# Level_Translators.net
KiCad netlist of a schematic drawn in Altium Designer
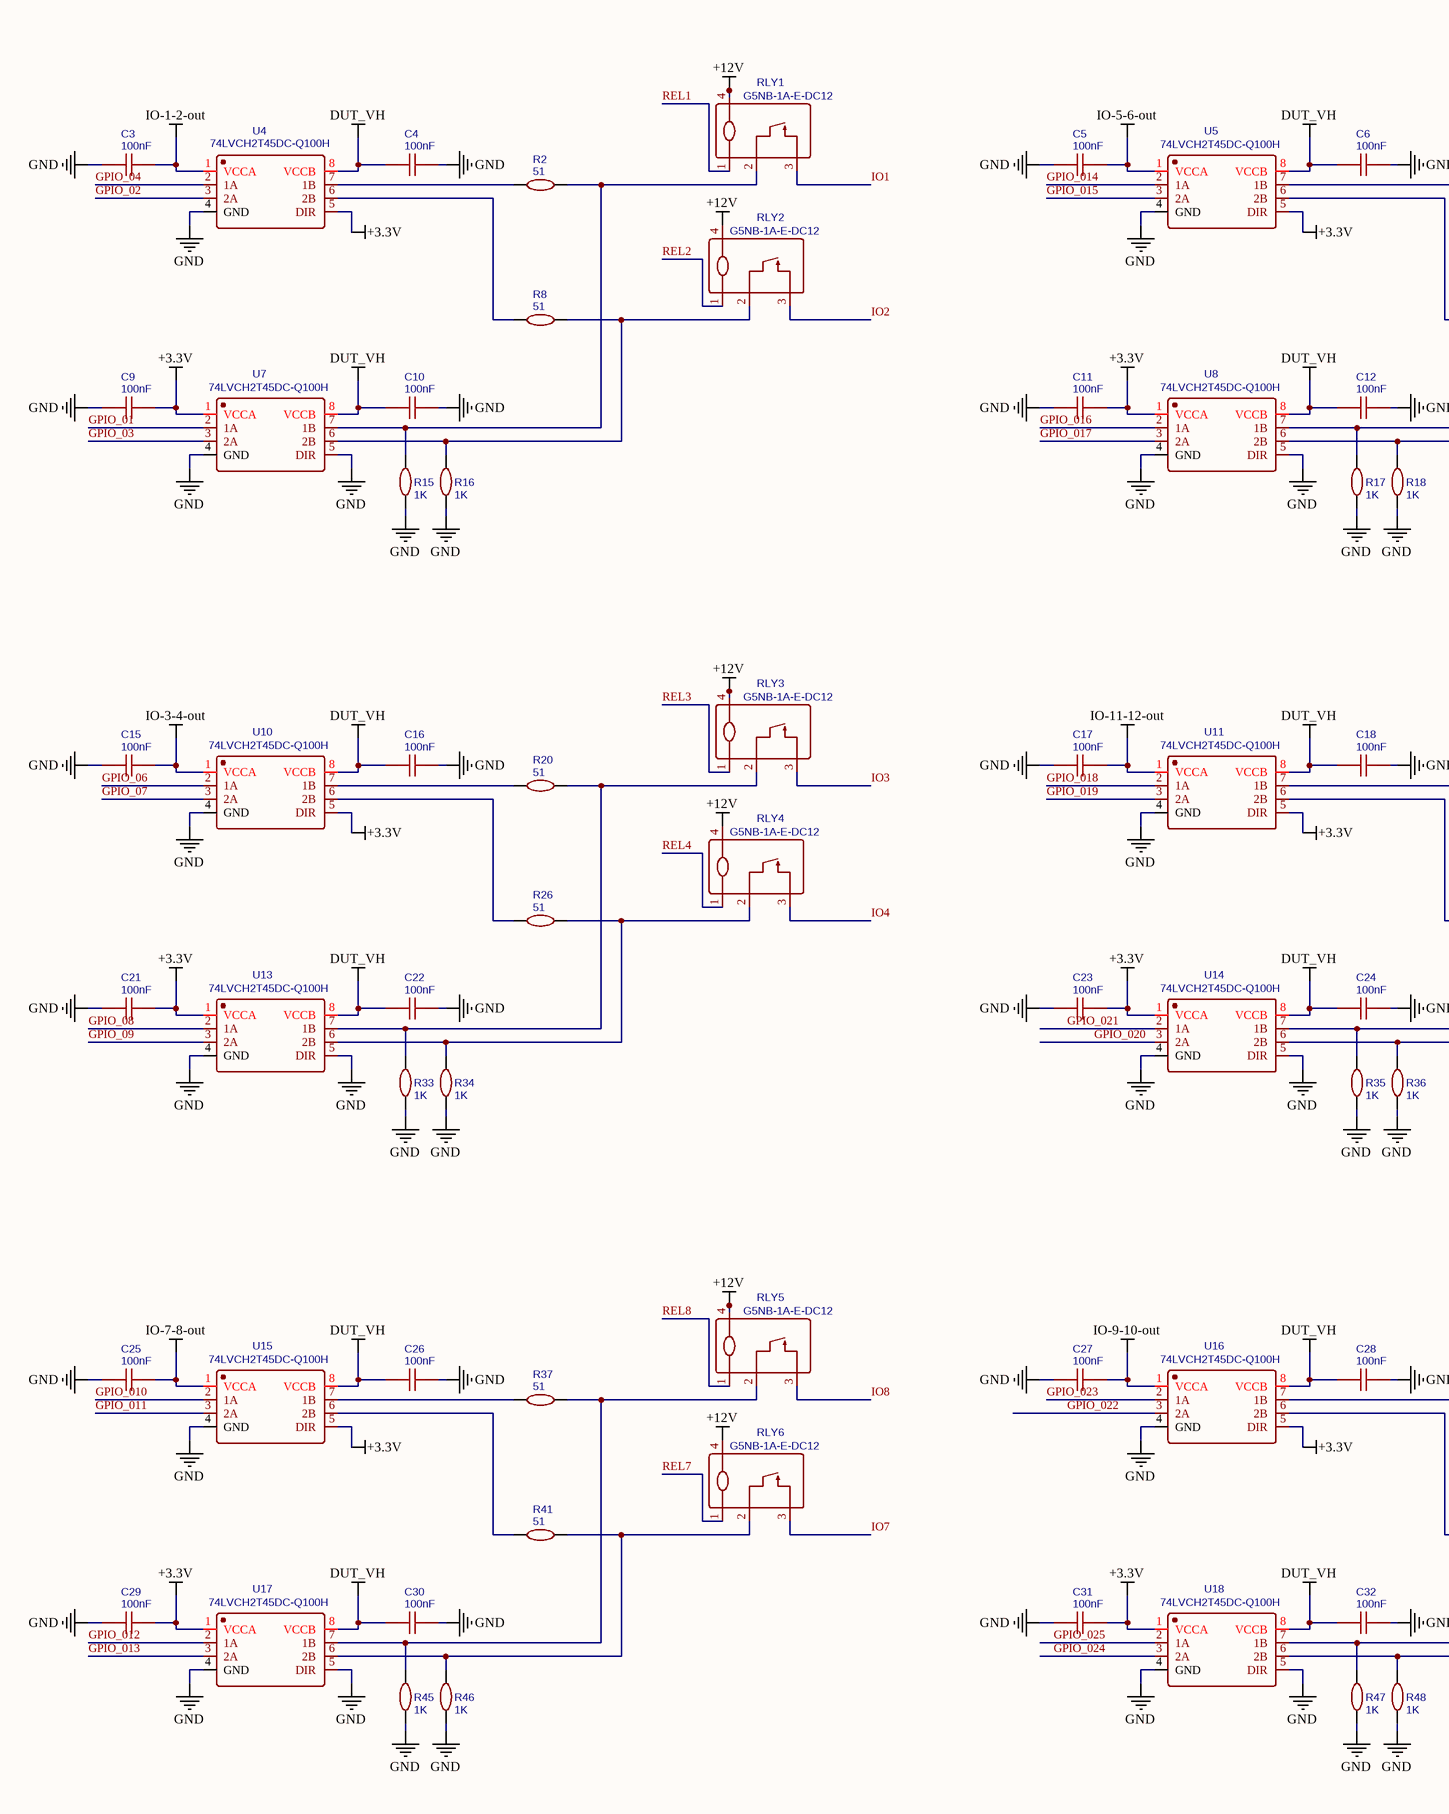
[diagram p0: Level Translators.SchDoc, left]
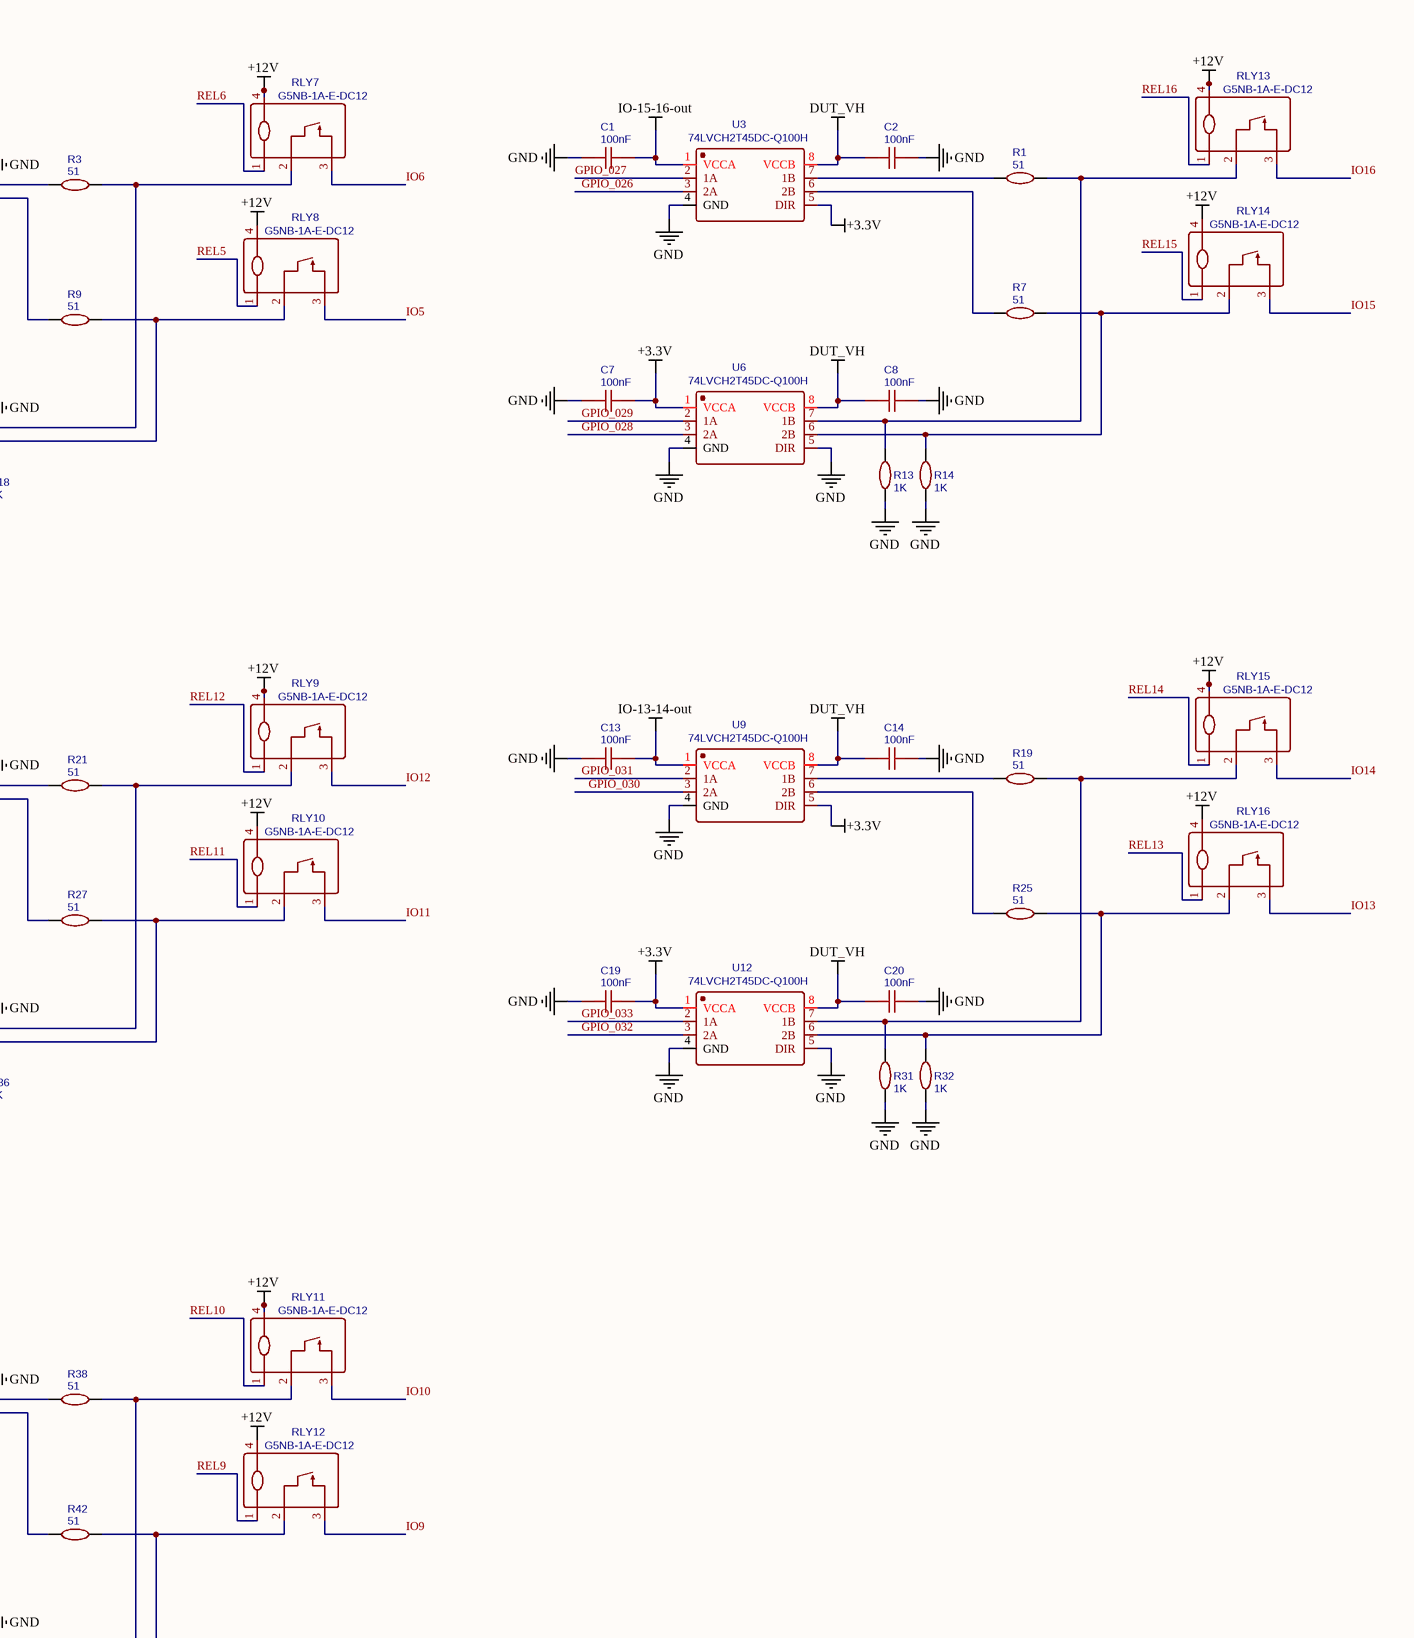
[diagram p1: Level Translators.SchDoc, right]

(export (version "E")
  (design (tool "Eeschema 10.0.6"))
  (components
    (comp (ref "C1")
      (value "100nF")
      (footprint "C0603")
      (fields
        (field (name "MANUFACTURER") "YAGEO")
        (field (name "MANUFACTURE PART NUMBER") "CC0603KRX7R9BB104")
      )
      (libsource (lib "FPGA Interface Board") (part "100nF"))
    )
    (comp (ref "C2")
      (value "100nF")
      (footprint "C0603")
      (fields
        (field (name "MANUFACTURER") "YAGEO")
        (field (name "MANUFACTURE PART NUMBER") "CC0603KRX7R9BB104")
      )
      (libsource (lib "FPGA Interface Board") (part "100nF"))
    )
    (comp (ref "C3")
      (value "100nF")
      (footprint "C0603")
      (fields
        (field (name "MANUFACTURER") "YAGEO")
        (field (name "MANUFACTURE PART NUMBER") "CC0603KRX7R9BB104")
      )
      (libsource (lib "FPGA Interface Board") (part "100nF"))
    )
    (comp (ref "C4")
      (value "100nF")
      (footprint "C0603")
      (fields
        (field (name "MANUFACTURER") "YAGEO")
        (field (name "MANUFACTURE PART NUMBER") "CC0603KRX7R9BB104")
      )
      (libsource (lib "FPGA Interface Board") (part "100nF"))
    )
    (comp (ref "C5")
      (value "100nF")
      (footprint "C0603")
      (fields
        (field (name "MANUFACTURER") "YAGEO")
        (field (name "MANUFACTURE PART NUMBER") "CC0603KRX7R9BB104")
      )
      (libsource (lib "FPGA Interface Board") (part "100nF"))
    )
    (comp (ref "C6")
      (value "100nF")
      (footprint "C0603")
      (fields
        (field (name "MANUFACTURER") "YAGEO")
        (field (name "MANUFACTURE PART NUMBER") "CC0603KRX7R9BB104")
      )
      (libsource (lib "FPGA Interface Board") (part "100nF"))
    )
    (comp (ref "C7")
      (value "100nF")
      (footprint "C0603")
      (fields
        (field (name "MANUFACTURER") "YAGEO")
        (field (name "MANUFACTURE PART NUMBER") "CC0603KRX7R9BB104")
      )
      (libsource (lib "FPGA Interface Board") (part "100nF"))
    )
    (comp (ref "C8")
      (value "100nF")
      (footprint "C0603")
      (fields
        (field (name "MANUFACTURER") "YAGEO")
        (field (name "MANUFACTURE PART NUMBER") "CC0603KRX7R9BB104")
      )
      (libsource (lib "FPGA Interface Board") (part "100nF"))
    )
    (comp (ref "C9")
      (value "100nF")
      (footprint "C0603")
      (fields
        (field (name "MANUFACTURER") "YAGEO")
        (field (name "MANUFACTURE PART NUMBER") "CC0603KRX7R9BB104")
      )
      (libsource (lib "FPGA Interface Board") (part "100nF"))
    )
    (comp (ref "C10")
      (value "100nF")
      (footprint "C0603")
      (fields
        (field (name "MANUFACTURER") "YAGEO")
        (field (name "MANUFACTURE PART NUMBER") "CC0603KRX7R9BB104")
      )
      (libsource (lib "FPGA Interface Board") (part "100nF"))
    )
    (comp (ref "C11")
      (value "100nF")
      (footprint "C0603")
      (fields
        (field (name "MANUFACTURER") "YAGEO")
        (field (name "MANUFACTURE PART NUMBER") "CC0603KRX7R9BB104")
      )
      (libsource (lib "FPGA Interface Board") (part "100nF"))
    )
    (comp (ref "C12")
      (value "100nF")
      (footprint "C0603")
      (fields
        (field (name "MANUFACTURER") "YAGEO")
        (field (name "MANUFACTURE PART NUMBER") "CC0603KRX7R9BB104")
      )
      (libsource (lib "FPGA Interface Board") (part "100nF"))
    )
    (comp (ref "C13")
      (value "100nF")
      (footprint "C0603")
      (fields
        (field (name "MANUFACTURER") "YAGEO")
        (field (name "MANUFACTURE PART NUMBER") "CC0603KRX7R9BB104")
      )
      (libsource (lib "FPGA Interface Board") (part "100nF"))
    )
    (comp (ref "C14")
      (value "100nF")
      (footprint "C0603")
      (fields
        (field (name "MANUFACTURER") "YAGEO")
        (field (name "MANUFACTURE PART NUMBER") "CC0603KRX7R9BB104")
      )
      (libsource (lib "FPGA Interface Board") (part "100nF"))
    )
    (comp (ref "C15")
      (value "100nF")
      (footprint "C0603")
      (fields
        (field (name "MANUFACTURER") "YAGEO")
        (field (name "MANUFACTURE PART NUMBER") "CC0603KRX7R9BB104")
      )
      (libsource (lib "FPGA Interface Board") (part "100nF"))
    )
    (comp (ref "C16")
      (value "100nF")
      (footprint "C0603")
      (fields
        (field (name "MANUFACTURER") "YAGEO")
        (field (name "MANUFACTURE PART NUMBER") "CC0603KRX7R9BB104")
      )
      (libsource (lib "FPGA Interface Board") (part "100nF"))
    )
    (comp (ref "C17")
      (value "100nF")
      (footprint "C0603")
      (fields
        (field (name "MANUFACTURER") "YAGEO")
        (field (name "MANUFACTURE PART NUMBER") "CC0603KRX7R9BB104")
      )
      (libsource (lib "FPGA Interface Board") (part "100nF"))
    )
    (comp (ref "C18")
      (value "100nF")
      (footprint "C0603")
      (fields
        (field (name "MANUFACTURER") "YAGEO")
        (field (name "MANUFACTURE PART NUMBER") "CC0603KRX7R9BB104")
      )
      (libsource (lib "FPGA Interface Board") (part "100nF"))
    )
    (comp (ref "C19")
      (value "100nF")
      (footprint "C0603")
      (fields
        (field (name "MANUFACTURER") "YAGEO")
        (field (name "MANUFACTURE PART NUMBER") "CC0603KRX7R9BB104")
      )
      (libsource (lib "FPGA Interface Board") (part "100nF"))
    )
    (comp (ref "C20")
      (value "100nF")
      (footprint "C0603")
      (fields
        (field (name "MANUFACTURER") "YAGEO")
        (field (name "MANUFACTURE PART NUMBER") "CC0603KRX7R9BB104")
      )
      (libsource (lib "FPGA Interface Board") (part "100nF"))
    )
    (comp (ref "C21")
      (value "100nF")
      (footprint "C0603")
      (fields
        (field (name "MANUFACTURER") "YAGEO")
        (field (name "MANUFACTURE PART NUMBER") "CC0603KRX7R9BB104")
      )
      (libsource (lib "FPGA Interface Board") (part "100nF"))
    )
    (comp (ref "C22")
      (value "100nF")
      (footprint "C0603")
      (fields
        (field (name "MANUFACTURER") "YAGEO")
        (field (name "MANUFACTURE PART NUMBER") "CC0603KRX7R9BB104")
      )
      (libsource (lib "FPGA Interface Board") (part "100nF"))
    )
    (comp (ref "C23")
      (value "100nF")
      (footprint "C0603")
      (fields
        (field (name "MANUFACTURER") "YAGEO")
        (field (name "MANUFACTURE PART NUMBER") "CC0603KRX7R9BB104")
      )
      (libsource (lib "FPGA Interface Board") (part "100nF"))
    )
    (comp (ref "C24")
      (value "100nF")
      (footprint "C0603")
      (fields
        (field (name "MANUFACTURER") "YAGEO")
        (field (name "MANUFACTURE PART NUMBER") "CC0603KRX7R9BB104")
      )
      (libsource (lib "FPGA Interface Board") (part "100nF"))
    )
    (comp (ref "C25")
      (value "100nF")
      (footprint "C0603")
      (fields
        (field (name "MANUFACTURER") "YAGEO")
        (field (name "MANUFACTURE PART NUMBER") "CC0603KRX7R9BB104")
      )
      (libsource (lib "FPGA Interface Board") (part "100nF"))
    )
    (comp (ref "C26")
      (value "100nF")
      (footprint "C0603")
      (fields
        (field (name "MANUFACTURER") "YAGEO")
        (field (name "MANUFACTURE PART NUMBER") "CC0603KRX7R9BB104")
      )
      (libsource (lib "FPGA Interface Board") (part "100nF"))
    )
    (comp (ref "C27")
      (value "100nF")
      (footprint "C0603")
      (fields
        (field (name "MANUFACTURER") "YAGEO")
        (field (name "MANUFACTURE PART NUMBER") "CC0603KRX7R9BB104")
      )
      (libsource (lib "FPGA Interface Board") (part "100nF"))
    )
    (comp (ref "C28")
      (value "100nF")
      (footprint "C0603")
      (fields
        (field (name "MANUFACTURER") "YAGEO")
        (field (name "MANUFACTURE PART NUMBER") "CC0603KRX7R9BB104")
      )
      (libsource (lib "FPGA Interface Board") (part "100nF"))
    )
    (comp (ref "C29")
      (value "100nF")
      (footprint "C0603")
      (fields
        (field (name "MANUFACTURER") "YAGEO")
        (field (name "MANUFACTURE PART NUMBER") "CC0603KRX7R9BB104")
      )
      (libsource (lib "FPGA Interface Board") (part "100nF"))
    )
    (comp (ref "C30")
      (value "100nF")
      (footprint "C0603")
      (fields
        (field (name "MANUFACTURER") "YAGEO")
        (field (name "MANUFACTURE PART NUMBER") "CC0603KRX7R9BB104")
      )
      (libsource (lib "FPGA Interface Board") (part "100nF"))
    )
    (comp (ref "C31")
      (value "100nF")
      (footprint "C0603")
      (fields
        (field (name "MANUFACTURER") "YAGEO")
        (field (name "MANUFACTURE PART NUMBER") "CC0603KRX7R9BB104")
      )
      (libsource (lib "FPGA Interface Board") (part "100nF"))
    )
    (comp (ref "C32")
      (value "100nF")
      (footprint "C0603")
      (fields
        (field (name "MANUFACTURER") "YAGEO")
        (field (name "MANUFACTURE PART NUMBER") "CC0603KRX7R9BB104")
      )
      (libsource (lib "FPGA Interface Board") (part "100nF"))
    )
    (comp (ref "R1")
      (value "51")
      (footprint "R0603")
      (fields
        (field (name "MANUFACTURER") "UniOhm")
        (field (name "MANUFACTURE PART NUMBER") "0603WAF510JT5E")
      )
      (libsource (lib "FPGA Interface Board") (part "51"))
    )
    (comp (ref "R2")
      (value "51")
      (footprint "R0603")
      (fields
        (field (name "MANUFACTURER") "UniOhm")
        (field (name "MANUFACTURE PART NUMBER") "0603WAF510JT5E")
      )
      (libsource (lib "FPGA Interface Board") (part "51"))
    )
    (comp (ref "R3")
      (value "51")
      (footprint "R0603")
      (fields
        (field (name "MANUFACTURER") "UniOhm")
        (field (name "MANUFACTURE PART NUMBER") "0603WAF510JT5E")
      )
      (libsource (lib "FPGA Interface Board") (part "51"))
    )
    (comp (ref "R7")
      (value "51")
      (footprint "R0603")
      (fields
        (field (name "MANUFACTURER") "UniOhm")
        (field (name "MANUFACTURE PART NUMBER") "0603WAF510JT5E")
      )
      (libsource (lib "FPGA Interface Board") (part "51"))
    )
    (comp (ref "R8")
      (value "51")
      (footprint "R0603")
      (fields
        (field (name "MANUFACTURER") "UniOhm")
        (field (name "MANUFACTURE PART NUMBER") "0603WAF510JT5E")
      )
      (libsource (lib "FPGA Interface Board") (part "51"))
    )
    (comp (ref "R9")
      (value "51")
      (footprint "R0603")
      (fields
        (field (name "MANUFACTURER") "UniOhm")
        (field (name "MANUFACTURE PART NUMBER") "0603WAF510JT5E")
      )
      (libsource (lib "FPGA Interface Board") (part "51"))
    )
    (comp (ref "R13")
      (value "1K")
      (footprint "R0603")
      (fields (field (name "MANUFACTURE PART NUMBER") "RC0603FR-071KL") (field (name "MANUFACTURER") "YAGEO"))
      (libsource (lib "FPGA Interface Board") (part "1K"))
    )
    (comp (ref "R14")
      (value "1K")
      (footprint "R0603")
      (fields (field (name "MANUFACTURE PART NUMBER") "RC0603FR-071KL") (field (name "MANUFACTURER") "YAGEO"))
      (libsource (lib "FPGA Interface Board") (part "1K"))
    )
    (comp (ref "R15")
      (value "1K")
      (footprint "R0603")
      (fields (field (name "MANUFACTURE PART NUMBER") "RC0603FR-071KL") (field (name "MANUFACTURER") "YAGEO"))
      (libsource (lib "FPGA Interface Board") (part "1K"))
    )
    (comp (ref "R16")
      (value "1K")
      (footprint "R0603")
      (fields (field (name "MANUFACTURE PART NUMBER") "RC0603FR-071KL") (field (name "MANUFACTURER") "YAGEO"))
      (libsource (lib "FPGA Interface Board") (part "1K"))
    )
    (comp (ref "R17")
      (value "1K")
      (footprint "R0603")
      (fields (field (name "MANUFACTURE PART NUMBER") "RC0603FR-071KL") (field (name "MANUFACTURER") "YAGEO"))
      (libsource (lib "FPGA Interface Board") (part "1K"))
    )
    (comp (ref "R18")
      (value "1K")
      (footprint "R0603")
      (fields (field (name "MANUFACTURE PART NUMBER") "RC0603FR-071KL") (field (name "MANUFACTURER") "YAGEO"))
      (libsource (lib "FPGA Interface Board") (part "1K"))
    )
    (comp (ref "R19")
      (value "51")
      (footprint "R0603")
      (fields
        (field (name "MANUFACTURER") "UniOhm")
        (field (name "MANUFACTURE PART NUMBER") "0603WAF510JT5E")
      )
      (libsource (lib "FPGA Interface Board") (part "51"))
    )
    (comp (ref "R20")
      (value "51")
      (footprint "R0603")
      (fields
        (field (name "MANUFACTURER") "UniOhm")
        (field (name "MANUFACTURE PART NUMBER") "0603WAF510JT5E")
      )
      (libsource (lib "FPGA Interface Board") (part "51"))
    )
    (comp (ref "R21")
      (value "51")
      (footprint "R0603")
      (fields
        (field (name "MANUFACTURER") "UniOhm")
        (field (name "MANUFACTURE PART NUMBER") "0603WAF510JT5E")
      )
      (libsource (lib "FPGA Interface Board") (part "51"))
    )
    (comp (ref "R25")
      (value "51")
      (footprint "R0603")
      (fields
        (field (name "MANUFACTURER") "UniOhm")
        (field (name "MANUFACTURE PART NUMBER") "0603WAF510JT5E")
      )
      (libsource (lib "FPGA Interface Board") (part "51"))
    )
    (comp (ref "R26")
      (value "51")
      (footprint "R0603")
      (fields
        (field (name "MANUFACTURER") "UniOhm")
        (field (name "MANUFACTURE PART NUMBER") "0603WAF510JT5E")
      )
      (libsource (lib "FPGA Interface Board") (part "51"))
    )
    (comp (ref "R27")
      (value "51")
      (footprint "R0603")
      (fields
        (field (name "MANUFACTURER") "UniOhm")
        (field (name "MANUFACTURE PART NUMBER") "0603WAF510JT5E")
      )
      (libsource (lib "FPGA Interface Board") (part "51"))
    )
    (comp (ref "R31")
      (value "1K")
      (footprint "R0603")
      (fields (field (name "MANUFACTURE PART NUMBER") "RC0603FR-071KL") (field (name "MANUFACTURER") "YAGEO"))
      (libsource (lib "FPGA Interface Board") (part "1K"))
    )
    (comp (ref "R32")
      (value "1K")
      (footprint "R0603")
      (fields (field (name "MANUFACTURE PART NUMBER") "RC0603FR-071KL") (field (name "MANUFACTURER") "YAGEO"))
      (libsource (lib "FPGA Interface Board") (part "1K"))
    )
    (comp (ref "R33")
      (value "1K")
      (footprint "R0603")
      (fields (field (name "MANUFACTURE PART NUMBER") "RC0603FR-071KL") (field (name "MANUFACTURER") "YAGEO"))
      (libsource (lib "FPGA Interface Board") (part "1K"))
    )
    (comp (ref "R34")
      (value "1K")
      (footprint "R0603")
      (fields (field (name "MANUFACTURE PART NUMBER") "RC0603FR-071KL") (field (name "MANUFACTURER") "YAGEO"))
      (libsource (lib "FPGA Interface Board") (part "1K"))
    )
    (comp (ref "R35")
      (value "1K")
      (footprint "R0603")
      (fields (field (name "MANUFACTURE PART NUMBER") "RC0603FR-071KL") (field (name "MANUFACTURER") "YAGEO"))
      (libsource (lib "FPGA Interface Board") (part "1K"))
    )
    (comp (ref "R36")
      (value "1K")
      (footprint "R0603")
      (fields (field (name "MANUFACTURE PART NUMBER") "RC0603FR-071KL") (field (name "MANUFACTURER") "YAGEO"))
      (libsource (lib "FPGA Interface Board") (part "1K"))
    )
    (comp (ref "R37")
      (value "51")
      (footprint "R0603")
      (fields
        (field (name "MANUFACTURER") "UniOhm")
        (field (name "MANUFACTURE PART NUMBER") "0603WAF510JT5E")
      )
      (libsource (lib "FPGA Interface Board") (part "51"))
    )
    (comp (ref "R38")
      (value "51")
      (footprint "R0603")
      (fields
        (field (name "MANUFACTURER") "UniOhm")
        (field (name "MANUFACTURE PART NUMBER") "0603WAF510JT5E")
      )
      (libsource (lib "FPGA Interface Board") (part "51"))
    )
    (comp (ref "R41")
      (value "51")
      (footprint "R0603")
      (fields
        (field (name "MANUFACTURER") "UniOhm")
        (field (name "MANUFACTURE PART NUMBER") "0603WAF510JT5E")
      )
      (libsource (lib "FPGA Interface Board") (part "51"))
    )
    (comp (ref "R42")
      (value "51")
      (footprint "R0603")
      (fields
        (field (name "MANUFACTURER") "UniOhm")
        (field (name "MANUFACTURE PART NUMBER") "0603WAF510JT5E")
      )
      (libsource (lib "FPGA Interface Board") (part "51"))
    )
    (comp (ref "R45")
      (value "1K")
      (footprint "R0603")
      (fields (field (name "MANUFACTURE PART NUMBER") "RC0603FR-071KL") (field (name "MANUFACTURER") "YAGEO"))
      (libsource (lib "FPGA Interface Board") (part "1K"))
    )
    (comp (ref "R46")
      (value "1K")
      (footprint "R0603")
      (fields (field (name "MANUFACTURE PART NUMBER") "RC0603FR-071KL") (field (name "MANUFACTURER") "YAGEO"))
      (libsource (lib "FPGA Interface Board") (part "1K"))
    )
    (comp (ref "R47")
      (value "1K")
      (footprint "R0603")
      (fields (field (name "MANUFACTURE PART NUMBER") "RC0603FR-071KL") (field (name "MANUFACTURER") "YAGEO"))
      (libsource (lib "FPGA Interface Board") (part "1K"))
    )
    (comp (ref "R48")
      (value "1K")
      (footprint "R0603")
      (fields (field (name "MANUFACTURE PART NUMBER") "RC0603FR-071KL") (field (name "MANUFACTURER") "YAGEO"))
      (libsource (lib "FPGA Interface Board") (part "1K"))
    )
    (comp (ref "RLY1")
      (value "G5NB-1A-E-DC12")
      (footprint "RELAY-TH_G5NB-1A-E-DCXX")
      (fields (field (name "MANUFACTURER") "Omron Electronics") (field (name "CONTRIBUTOR") "LCSC"))
      (libsource (lib "FPGA Interface Board") (part "G5NB-1A-E-DC12"))
    )
    (comp (ref "RLY2")
      (value "G5NB-1A-E-DC12")
      (footprint "RELAY-TH_G5NB-1A-E-DCXX")
      (fields (field (name "MANUFACTURER") "Omron Electronics") (field (name "CONTRIBUTOR") "LCSC"))
      (libsource (lib "FPGA Interface Board") (part "G5NB-1A-E-DC12"))
    )
    (comp (ref "RLY3")
      (value "G5NB-1A-E-DC12")
      (footprint "RELAY-TH_G5NB-1A-E-DCXX")
      (fields (field (name "MANUFACTURER") "Omron Electronics") (field (name "CONTRIBUTOR") "LCSC"))
      (libsource (lib "FPGA Interface Board") (part "G5NB-1A-E-DC12"))
    )
    (comp (ref "RLY4")
      (value "G5NB-1A-E-DC12")
      (footprint "RELAY-TH_G5NB-1A-E-DCXX")
      (fields (field (name "MANUFACTURER") "Omron Electronics") (field (name "CONTRIBUTOR") "LCSC"))
      (libsource (lib "FPGA Interface Board") (part "G5NB-1A-E-DC12"))
    )
    (comp (ref "RLY5")
      (value "G5NB-1A-E-DC12")
      (footprint "RELAY-TH_G5NB-1A-E-DCXX")
      (fields (field (name "MANUFACTURER") "Omron Electronics") (field (name "CONTRIBUTOR") "LCSC"))
      (libsource (lib "FPGA Interface Board") (part "G5NB-1A-E-DC12"))
    )
    (comp (ref "RLY6")
      (value "G5NB-1A-E-DC12")
      (footprint "RELAY-TH_G5NB-1A-E-DCXX")
      (fields (field (name "MANUFACTURER") "Omron Electronics") (field (name "CONTRIBUTOR") "LCSC"))
      (libsource (lib "FPGA Interface Board") (part "G5NB-1A-E-DC12"))
    )
    (comp (ref "RLY7")
      (value "G5NB-1A-E-DC12")
      (footprint "RELAY-TH_G5NB-1A-E-DCXX")
      (fields (field (name "MANUFACTURER") "Omron Electronics") (field (name "CONTRIBUTOR") "LCSC"))
      (libsource (lib "FPGA Interface Board") (part "G5NB-1A-E-DC12"))
    )
    (comp (ref "RLY8")
      (value "G5NB-1A-E-DC12")
      (footprint "RELAY-TH_G5NB-1A-E-DCXX")
      (fields (field (name "MANUFACTURER") "Omron Electronics") (field (name "CONTRIBUTOR") "LCSC"))
      (libsource (lib "FPGA Interface Board") (part "G5NB-1A-E-DC12"))
    )
    (comp (ref "RLY9")
      (value "G5NB-1A-E-DC12")
      (footprint "RELAY-TH_G5NB-1A-E-DCXX")
      (fields (field (name "MANUFACTURER") "Omron Electronics") (field (name "CONTRIBUTOR") "LCSC"))
      (libsource (lib "FPGA Interface Board") (part "G5NB-1A-E-DC12"))
    )
    (comp (ref "RLY10")
      (value "G5NB-1A-E-DC12")
      (footprint "RELAY-TH_G5NB-1A-E-DCXX")
      (fields (field (name "MANUFACTURER") "Omron Electronics") (field (name "CONTRIBUTOR") "LCSC"))
      (libsource (lib "FPGA Interface Board") (part "G5NB-1A-E-DC12"))
    )
    (comp (ref "RLY11")
      (value "G5NB-1A-E-DC12")
      (footprint "RELAY-TH_G5NB-1A-E-DCXX")
      (fields (field (name "MANUFACTURER") "Omron Electronics") (field (name "CONTRIBUTOR") "LCSC"))
      (libsource (lib "FPGA Interface Board") (part "G5NB-1A-E-DC12"))
    )
    (comp (ref "RLY12")
      (value "G5NB-1A-E-DC12")
      (footprint "RELAY-TH_G5NB-1A-E-DCXX")
      (fields (field (name "MANUFACTURER") "Omron Electronics") (field (name "CONTRIBUTOR") "LCSC"))
      (libsource (lib "FPGA Interface Board") (part "G5NB-1A-E-DC12"))
    )
    (comp (ref "RLY13")
      (value "G5NB-1A-E-DC12")
      (footprint "RELAY-TH_G5NB-1A-E-DCXX")
      (fields (field (name "MANUFACTURER") "Omron Electronics") (field (name "CONTRIBUTOR") "LCSC"))
      (libsource (lib "FPGA Interface Board") (part "G5NB-1A-E-DC12"))
    )
    (comp (ref "RLY14")
      (value "G5NB-1A-E-DC12")
      (footprint "RELAY-TH_G5NB-1A-E-DCXX")
      (fields (field (name "MANUFACTURER") "Omron Electronics") (field (name "CONTRIBUTOR") "LCSC"))
      (libsource (lib "FPGA Interface Board") (part "G5NB-1A-E-DC12"))
    )
    (comp (ref "RLY15")
      (value "G5NB-1A-E-DC12")
      (footprint "RELAY-TH_G5NB-1A-E-DCXX")
      (fields (field (name "MANUFACTURER") "Omron Electronics") (field (name "CONTRIBUTOR") "LCSC"))
      (libsource (lib "FPGA Interface Board") (part "G5NB-1A-E-DC12"))
    )
    (comp (ref "RLY16")
      (value "G5NB-1A-E-DC12")
      (footprint "RELAY-TH_G5NB-1A-E-DCXX")
      (fields (field (name "MANUFACTURER") "Omron Electronics") (field (name "CONTRIBUTOR") "LCSC"))
      (libsource (lib "FPGA Interface Board") (part "G5NB-1A-E-DC12"))
    )
    (comp (ref "U3")
      (value "74LVCH2T45DC-Q100H")
      (footprint "VSSOP-8_L2.4-W2.1-P0.50-LS3.2-BR")
      (fields (field (name "MANUFACTURER") "Nexperia") (field (name "CONTRIBUTOR") "LCSC"))
      (libsource (lib "FPGA Interface Board") (part "74LVCH2T45DC-Q100H"))
    )
    (comp (ref "U4")
      (value "74LVCH2T45DC-Q100H")
      (footprint "VSSOP-8_L2.4-W2.1-P0.50-LS3.2-BR")
      (fields (field (name "MANUFACTURER") "Nexperia") (field (name "CONTRIBUTOR") "LCSC"))
      (libsource (lib "FPGA Interface Board") (part "74LVCH2T45DC-Q100H"))
    )
    (comp (ref "U5")
      (value "74LVCH2T45DC-Q100H")
      (footprint "VSSOP-8_L2.4-W2.1-P0.50-LS3.2-BR")
      (fields (field (name "MANUFACTURER") "Nexperia") (field (name "CONTRIBUTOR") "LCSC"))
      (libsource (lib "FPGA Interface Board") (part "74LVCH2T45DC-Q100H"))
    )
    (comp (ref "U6")
      (value "74LVCH2T45DC-Q100H")
      (footprint "VSSOP-8_L2.4-W2.1-P0.50-LS3.2-BR")
      (fields (field (name "MANUFACTURER") "Nexperia") (field (name "CONTRIBUTOR") "LCSC"))
      (libsource (lib "FPGA Interface Board") (part "74LVCH2T45DC-Q100H"))
    )
    (comp (ref "U7")
      (value "74LVCH2T45DC-Q100H")
      (footprint "VSSOP-8_L2.4-W2.1-P0.50-LS3.2-BR")
      (fields (field (name "MANUFACTURER") "Nexperia") (field (name "CONTRIBUTOR") "LCSC"))
      (libsource (lib "FPGA Interface Board") (part "74LVCH2T45DC-Q100H"))
    )
    (comp (ref "U8")
      (value "74LVCH2T45DC-Q100H")
      (footprint "VSSOP-8_L2.4-W2.1-P0.50-LS3.2-BR")
      (fields (field (name "MANUFACTURER") "Nexperia") (field (name "CONTRIBUTOR") "LCSC"))
      (libsource (lib "FPGA Interface Board") (part "74LVCH2T45DC-Q100H"))
    )
    (comp (ref "U9")
      (value "74LVCH2T45DC-Q100H")
      (footprint "VSSOP-8_L2.4-W2.1-P0.50-LS3.2-BR")
      (fields (field (name "MANUFACTURER") "Nexperia") (field (name "CONTRIBUTOR") "LCSC"))
      (libsource (lib "FPGA Interface Board") (part "74LVCH2T45DC-Q100H"))
    )
    (comp (ref "U10")
      (value "74LVCH2T45DC-Q100H")
      (footprint "VSSOP-8_L2.4-W2.1-P0.50-LS3.2-BR")
      (fields (field (name "MANUFACTURER") "Nexperia") (field (name "CONTRIBUTOR") "LCSC"))
      (libsource (lib "FPGA Interface Board") (part "74LVCH2T45DC-Q100H"))
    )
    (comp (ref "U11")
      (value "74LVCH2T45DC-Q100H")
      (footprint "VSSOP-8_L2.4-W2.1-P0.50-LS3.2-BR")
      (fields (field (name "MANUFACTURER") "Nexperia") (field (name "CONTRIBUTOR") "LCSC"))
      (libsource (lib "FPGA Interface Board") (part "74LVCH2T45DC-Q100H"))
    )
    (comp (ref "U12")
      (value "74LVCH2T45DC-Q100H")
      (footprint "VSSOP-8_L2.4-W2.1-P0.50-LS3.2-BR")
      (fields (field (name "MANUFACTURER") "Nexperia") (field (name "CONTRIBUTOR") "LCSC"))
      (libsource (lib "FPGA Interface Board") (part "74LVCH2T45DC-Q100H"))
    )
    (comp (ref "U13")
      (value "74LVCH2T45DC-Q100H")
      (footprint "VSSOP-8_L2.4-W2.1-P0.50-LS3.2-BR")
      (fields (field (name "MANUFACTURER") "Nexperia") (field (name "CONTRIBUTOR") "LCSC"))
      (libsource (lib "FPGA Interface Board") (part "74LVCH2T45DC-Q100H"))
    )
    (comp (ref "U14")
      (value "74LVCH2T45DC-Q100H")
      (footprint "VSSOP-8_L2.4-W2.1-P0.50-LS3.2-BR")
      (fields (field (name "MANUFACTURER") "Nexperia") (field (name "CONTRIBUTOR") "LCSC"))
      (libsource (lib "FPGA Interface Board") (part "74LVCH2T45DC-Q100H"))
    )
    (comp (ref "U15")
      (value "74LVCH2T45DC-Q100H")
      (footprint "VSSOP-8_L2.4-W2.1-P0.50-LS3.2-BR")
      (fields (field (name "MANUFACTURER") "Nexperia") (field (name "CONTRIBUTOR") "LCSC"))
      (libsource (lib "FPGA Interface Board") (part "74LVCH2T45DC-Q100H"))
    )
    (comp (ref "U16")
      (value "74LVCH2T45DC-Q100H")
      (footprint "VSSOP-8_L2.4-W2.1-P0.50-LS3.2-BR")
      (fields (field (name "MANUFACTURER") "Nexperia") (field (name "CONTRIBUTOR") "LCSC"))
      (libsource (lib "FPGA Interface Board") (part "74LVCH2T45DC-Q100H"))
    )
    (comp (ref "U17")
      (value "74LVCH2T45DC-Q100H")
      (footprint "VSSOP-8_L2.4-W2.1-P0.50-LS3.2-BR")
      (fields (field (name "MANUFACTURER") "Nexperia") (field (name "CONTRIBUTOR") "LCSC"))
      (libsource (lib "FPGA Interface Board") (part "74LVCH2T45DC-Q100H"))
    )
    (comp (ref "U18")
      (value "74LVCH2T45DC-Q100H")
      (footprint "VSSOP-8_L2.4-W2.1-P0.50-LS3.2-BR")
      (fields (field (name "MANUFACTURER") "Nexperia") (field (name "CONTRIBUTOR") "LCSC"))
      (libsource (lib "FPGA Interface Board") (part "74LVCH2T45DC-Q100H"))
    )
  )
  (nets
    (net (code "1") (name "+3.3V") (class "Default")
      (node (ref "C11") (pin "2") (pinfunction "2_2") (pintype "passive"))
      (node (ref "C19") (pin "2") (pinfunction "2_2") (pintype "passive"))
      (node (ref "C21") (pin "2") (pinfunction "2_2") (pintype "passive"))
      (node (ref "C23") (pin "2") (pinfunction "2_2") (pintype "passive"))
      (node (ref "C29") (pin "2") (pinfunction "2_2") (pintype "passive"))
      (node (ref "C31") (pin "2") (pinfunction "2_2") (pintype "passive"))
      (node (ref "C7") (pin "2") (pinfunction "2_2") (pintype "passive"))
      (node (ref "C9") (pin "2") (pinfunction "2_2") (pintype "passive"))
      (node (ref "U10") (pin "5") (pinfunction "DIR_5") (pintype "passive"))
      (node (ref "U11") (pin "5") (pinfunction "DIR_5") (pintype "passive"))
      (node (ref "U12") (pin "1") (pinfunction "VCCA_1") (pintype "passive"))
      (node (ref "U13") (pin "1") (pinfunction "VCCA_1") (pintype "passive"))
      (node (ref "U14") (pin "1") (pinfunction "VCCA_1") (pintype "passive"))
      (node (ref "U15") (pin "5") (pinfunction "DIR_5") (pintype "passive"))
      (node (ref "U16") (pin "5") (pinfunction "DIR_5") (pintype "passive"))
      (node (ref "U17") (pin "1") (pinfunction "VCCA_1") (pintype "passive"))
      (node (ref "U18") (pin "1") (pinfunction "VCCA_1") (pintype "passive"))
      (node (ref "U3") (pin "5") (pinfunction "DIR_5") (pintype "passive"))
      (node (ref "U4") (pin "5") (pinfunction "DIR_5") (pintype "passive"))
      (node (ref "U5") (pin "5") (pinfunction "DIR_5") (pintype "passive"))
      (node (ref "U6") (pin "1") (pinfunction "VCCA_1") (pintype "passive"))
      (node (ref "U7") (pin "1") (pinfunction "VCCA_1") (pintype "passive"))
      (node (ref "U8") (pin "1") (pinfunction "VCCA_1") (pintype "passive"))
      (node (ref "U9") (pin "5") (pinfunction "DIR_5") (pintype "passive"))
    )
    (net (code "2") (name "+12V") (class "Default")
      (node (ref "RLY1") (pin "4") (pinfunction "4_4") (pintype "passive"))
      (node (ref "RLY10") (pin "4") (pinfunction "4_4") (pintype "passive"))
      (node (ref "RLY11") (pin "4") (pinfunction "4_4") (pintype "passive"))
      (node (ref "RLY12") (pin "4") (pinfunction "4_4") (pintype "passive"))
      (node (ref "RLY13") (pin "4") (pinfunction "4_4") (pintype "passive"))
      (node (ref "RLY14") (pin "4") (pinfunction "4_4") (pintype "passive"))
      (node (ref "RLY15") (pin "4") (pinfunction "4_4") (pintype "passive"))
      (node (ref "RLY16") (pin "4") (pinfunction "4_4") (pintype "passive"))
      (node (ref "RLY2") (pin "4") (pinfunction "4_4") (pintype "passive"))
      (node (ref "RLY3") (pin "4") (pinfunction "4_4") (pintype "passive"))
      (node (ref "RLY4") (pin "4") (pinfunction "4_4") (pintype "passive"))
      (node (ref "RLY5") (pin "4") (pinfunction "4_4") (pintype "passive"))
      (node (ref "RLY6") (pin "4") (pinfunction "4_4") (pintype "passive"))
      (node (ref "RLY7") (pin "4") (pinfunction "4_4") (pintype "passive"))
      (node (ref "RLY8") (pin "4") (pinfunction "4_4") (pintype "passive"))
      (node (ref "RLY9") (pin "4") (pinfunction "4_4") (pintype "passive"))
    )
    (net (code "3") (name "/GPIO_01") (class "Default")
      (node (ref "U7") (pin "2") (pinfunction "1A_2") (pintype "passive"))
    )
    (net (code "4") (name "/GPIO_02") (class "Default")
      (node (ref "U4") (pin "3") (pinfunction "2A_3") (pintype "passive"))
    )
    (net (code "5") (name "/GPIO_03") (class "Default")
      (node (ref "U7") (pin "3") (pinfunction "2A_3") (pintype "passive"))
    )
    (net (code "6") (name "/GPIO_04") (class "Default")
      (node (ref "U4") (pin "2") (pinfunction "1A_2") (pintype "passive"))
    )
    (net (code "7") (name "/GPIO_06") (class "Default")
      (node (ref "U10") (pin "2") (pinfunction "1A_2") (pintype "passive"))
    )
    (net (code "8") (name "/GPIO_07") (class "Default")
      (node (ref "U10") (pin "3") (pinfunction "2A_3") (pintype "passive"))
    )
    (net (code "9") (name "/GPIO_08") (class "Default")
      (node (ref "U13") (pin "2") (pinfunction "1A_2") (pintype "passive"))
    )
    (net (code "10") (name "/GPIO_09") (class "Default")
      (node (ref "U13") (pin "3") (pinfunction "2A_3") (pintype "passive"))
    )
    (net (code "11") (name "/GPIO_010") (class "Default")
      (node (ref "U15") (pin "2") (pinfunction "1A_2") (pintype "passive"))
    )
    (net (code "12") (name "/GPIO_011") (class "Default")
      (node (ref "U15") (pin "3") (pinfunction "2A_3") (pintype "passive"))
    )
    (net (code "13") (name "/GPIO_012") (class "Default")
      (node (ref "U17") (pin "2") (pinfunction "1A_2") (pintype "passive"))
    )
    (net (code "14") (name "/GPIO_013") (class "Default")
      (node (ref "U17") (pin "3") (pinfunction "2A_3") (pintype "passive"))
    )
    (net (code "15") (name "/GPIO_014") (class "Default")
      (node (ref "U5") (pin "2") (pinfunction "1A_2") (pintype "passive"))
    )
    (net (code "16") (name "/GPIO_015") (class "Default")
      (node (ref "U5") (pin "3") (pinfunction "2A_3") (pintype "passive"))
    )
    (net (code "17") (name "/GPIO_016") (class "Default")
      (node (ref "U8") (pin "2") (pinfunction "1A_2") (pintype "passive"))
    )
    (net (code "18") (name "/GPIO_017") (class "Default")
      (node (ref "U8") (pin "3") (pinfunction "2A_3") (pintype "passive"))
    )
    (net (code "19") (name "/GPIO_018") (class "Default")
      (node (ref "U11") (pin "2") (pinfunction "1A_2") (pintype "passive"))
    )
    (net (code "20") (name "/GPIO_019") (class "Default")
      (node (ref "U11") (pin "3") (pinfunction "2A_3") (pintype "passive"))
    )
    (net (code "21") (name "/GPIO_020") (class "Default")
      (node (ref "U14") (pin "3") (pinfunction "2A_3") (pintype "passive"))
    )
    (net (code "22") (name "/GPIO_021") (class "Default")
      (node (ref "U14") (pin "2") (pinfunction "1A_2") (pintype "passive"))
    )
    (net (code "23") (name "/GPIO_022") (class "Default")
      (node (ref "U16") (pin "3") (pinfunction "2A_3") (pintype "passive"))
    )
    (net (code "24") (name "/GPIO_023") (class "Default")
      (node (ref "U16") (pin "2") (pinfunction "1A_2") (pintype "passive"))
    )
    (net (code "25") (name "/GPIO_024") (class "Default")
      (node (ref "U18") (pin "3") (pinfunction "2A_3") (pintype "passive"))
    )
    (net (code "26") (name "/GPIO_025") (class "Default")
      (node (ref "U18") (pin "2") (pinfunction "1A_2") (pintype "passive"))
    )
    (net (code "27") (name "/GPIO_026") (class "Default")
      (node (ref "U3") (pin "3") (pinfunction "2A_3") (pintype "passive"))
    )
    (net (code "28") (name "/GPIO_027") (class "Default")
      (node (ref "U3") (pin "2") (pinfunction "1A_2") (pintype "passive"))
    )
    (net (code "29") (name "/GPIO_028") (class "Default")
      (node (ref "U6") (pin "3") (pinfunction "2A_3") (pintype "passive"))
    )
    (net (code "30") (name "/GPIO_029") (class "Default")
      (node (ref "U6") (pin "2") (pinfunction "1A_2") (pintype "passive"))
    )
    (net (code "31") (name "/GPIO_030") (class "Default")
      (node (ref "U9") (pin "3") (pinfunction "2A_3") (pintype "passive"))
    )
    (net (code "32") (name "/GPIO_031") (class "Default")
      (node (ref "U9") (pin "2") (pinfunction "1A_2") (pintype "passive"))
    )
    (net (code "33") (name "/GPIO_032") (class "Default")
      (node (ref "U12") (pin "3") (pinfunction "2A_3") (pintype "passive"))
    )
    (net (code "34") (name "/GPIO_033") (class "Default")
      (node (ref "U12") (pin "2") (pinfunction "1A_2") (pintype "passive"))
    )
    (net (code "35") (name "/IO1") (class "Default")
      (node (ref "RLY1") (pin "3") (pinfunction "3_3") (pintype "passive"))
    )
    (net (code "36") (name "/IO2") (class "Default")
      (node (ref "RLY2") (pin "3") (pinfunction "3_3") (pintype "passive"))
    )
    (net (code "37") (name "/IO3") (class "Default")
      (node (ref "RLY3") (pin "3") (pinfunction "3_3") (pintype "passive"))
    )
    (net (code "38") (name "/IO4") (class "Default")
      (node (ref "RLY4") (pin "3") (pinfunction "3_3") (pintype "passive"))
    )
    (net (code "39") (name "/IO5") (class "Default")
      (node (ref "RLY8") (pin "3") (pinfunction "3_3") (pintype "passive"))
    )
    (net (code "40") (name "/IO6") (class "Default")
      (node (ref "RLY7") (pin "3") (pinfunction "3_3") (pintype "passive"))
    )
    (net (code "41") (name "/IO7") (class "Default")
      (node (ref "RLY6") (pin "3") (pinfunction "3_3") (pintype "passive"))
    )
    (net (code "42") (name "/IO8") (class "Default")
      (node (ref "RLY5") (pin "3") (pinfunction "3_3") (pintype "passive"))
    )
    (net (code "43") (name "/IO9") (class "Default")
      (node (ref "RLY12") (pin "3") (pinfunction "3_3") (pintype "passive"))
    )
    (net (code "44") (name "/IO10") (class "Default")
      (node (ref "RLY11") (pin "3") (pinfunction "3_3") (pintype "passive"))
    )
    (net (code "45") (name "/IO11") (class "Default")
      (node (ref "RLY10") (pin "3") (pinfunction "3_3") (pintype "passive"))
    )
    (net (code "46") (name "/IO12") (class "Default")
      (node (ref "RLY9") (pin "3") (pinfunction "3_3") (pintype "passive"))
    )
    (net (code "47") (name "/IO13") (class "Default")
      (node (ref "RLY16") (pin "3") (pinfunction "3_3") (pintype "passive"))
    )
    (net (code "48") (name "/IO14") (class "Default")
      (node (ref "RLY15") (pin "3") (pinfunction "3_3") (pintype "passive"))
    )
    (net (code "49") (name "/IO15") (class "Default")
      (node (ref "RLY14") (pin "3") (pinfunction "3_3") (pintype "passive"))
    )
    (net (code "50") (name "/IO16") (class "Default")
      (node (ref "RLY13") (pin "3") (pinfunction "3_3") (pintype "passive"))
    )
    (net (code "51") (name "/REL1") (class "Default")
      (node (ref "RLY1") (pin "1") (pinfunction "1_1") (pintype "passive"))
    )
    (net (code "52") (name "/REL2") (class "Default")
      (node (ref "RLY2") (pin "1") (pinfunction "1_1") (pintype "passive"))
    )
    (net (code "53") (name "/REL3") (class "Default")
      (node (ref "RLY3") (pin "1") (pinfunction "1_1") (pintype "passive"))
    )
    (net (code "54") (name "/REL4") (class "Default")
      (node (ref "RLY4") (pin "1") (pinfunction "1_1") (pintype "passive"))
    )
    (net (code "55") (name "/REL5") (class "Default")
      (node (ref "RLY8") (pin "1") (pinfunction "1_1") (pintype "passive"))
    )
    (net (code "56") (name "/REL6") (class "Default")
      (node (ref "RLY7") (pin "1") (pinfunction "1_1") (pintype "passive"))
    )
    (net (code "57") (name "/REL7") (class "Default")
      (node (ref "RLY6") (pin "1") (pinfunction "1_1") (pintype "passive"))
    )
    (net (code "58") (name "/REL8") (class "Default")
      (node (ref "RLY5") (pin "1") (pinfunction "1_1") (pintype "passive"))
    )
    (net (code "59") (name "/REL9") (class "Default")
      (node (ref "RLY12") (pin "1") (pinfunction "1_1") (pintype "passive"))
    )
    (net (code "60") (name "/REL10") (class "Default")
      (node (ref "RLY11") (pin "1") (pinfunction "1_1") (pintype "passive"))
    )
    (net (code "61") (name "/REL11") (class "Default")
      (node (ref "RLY10") (pin "1") (pinfunction "1_1") (pintype "passive"))
    )
    (net (code "62") (name "/REL12") (class "Default")
      (node (ref "RLY9") (pin "1") (pinfunction "1_1") (pintype "passive"))
    )
    (net (code "63") (name "/REL13") (class "Default")
      (node (ref "RLY16") (pin "1") (pinfunction "1_1") (pintype "passive"))
    )
    (net (code "64") (name "/REL14") (class "Default")
      (node (ref "RLY15") (pin "1") (pinfunction "1_1") (pintype "passive"))
    )
    (net (code "65") (name "/REL15") (class "Default")
      (node (ref "RLY14") (pin "1") (pinfunction "1_1") (pintype "passive"))
    )
    (net (code "66") (name "/REL16") (class "Default")
      (node (ref "RLY13") (pin "1") (pinfunction "1_1") (pintype "passive"))
    )
    (net (code "67") (name "DUT_VH") (class "Default")
      (node (ref "C10") (pin "1") (pinfunction "1_1") (pintype "passive"))
      (node (ref "C12") (pin "1") (pinfunction "1_1") (pintype "passive"))
      (node (ref "C14") (pin "1") (pinfunction "1_1") (pintype "passive"))
      (node (ref "C16") (pin "1") (pinfunction "1_1") (pintype "passive"))
      (node (ref "C18") (pin "1") (pinfunction "1_1") (pintype "passive"))
      (node (ref "C2") (pin "1") (pinfunction "1_1") (pintype "passive"))
      (node (ref "C20") (pin "1") (pinfunction "1_1") (pintype "passive"))
      (node (ref "C22") (pin "1") (pinfunction "1_1") (pintype "passive"))
      (node (ref "C24") (pin "1") (pinfunction "1_1") (pintype "passive"))
      (node (ref "C26") (pin "1") (pinfunction "1_1") (pintype "passive"))
      (node (ref "C28") (pin "1") (pinfunction "1_1") (pintype "passive"))
      (node (ref "C30") (pin "1") (pinfunction "1_1") (pintype "passive"))
      (node (ref "C32") (pin "1") (pinfunction "1_1") (pintype "passive"))
      (node (ref "C4") (pin "1") (pinfunction "1_1") (pintype "passive"))
      (node (ref "C6") (pin "1") (pinfunction "1_1") (pintype "passive"))
      (node (ref "C8") (pin "1") (pinfunction "1_1") (pintype "passive"))
      (node (ref "U10") (pin "8") (pinfunction "VCCB_8") (pintype "passive"))
      (node (ref "U11") (pin "8") (pinfunction "VCCB_8") (pintype "passive"))
      (node (ref "U12") (pin "8") (pinfunction "VCCB_8") (pintype "passive"))
      (node (ref "U13") (pin "8") (pinfunction "VCCB_8") (pintype "passive"))
      (node (ref "U14") (pin "8") (pinfunction "VCCB_8") (pintype "passive"))
      (node (ref "U15") (pin "8") (pinfunction "VCCB_8") (pintype "passive"))
      (node (ref "U16") (pin "8") (pinfunction "VCCB_8") (pintype "passive"))
      (node (ref "U17") (pin "8") (pinfunction "VCCB_8") (pintype "passive"))
      (node (ref "U18") (pin "8") (pinfunction "VCCB_8") (pintype "passive"))
      (node (ref "U3") (pin "8") (pinfunction "VCCB_8") (pintype "passive"))
      (node (ref "U4") (pin "8") (pinfunction "VCCB_8") (pintype "passive"))
      (node (ref "U5") (pin "8") (pinfunction "VCCB_8") (pintype "passive"))
      (node (ref "U6") (pin "8") (pinfunction "VCCB_8") (pintype "passive"))
      (node (ref "U7") (pin "8") (pinfunction "VCCB_8") (pintype "passive"))
      (node (ref "U8") (pin "8") (pinfunction "VCCB_8") (pintype "passive"))
      (node (ref "U9") (pin "8") (pinfunction "VCCB_8") (pintype "passive"))
    )
    (net (code "68") (name "GND") (class "Default")
      (node (ref "C1") (pin "1") (pinfunction "1_1") (pintype "passive"))
      (node (ref "C10") (pin "2") (pinfunction "2_2") (pintype "passive"))
      (node (ref "C11") (pin "1") (pinfunction "1_1") (pintype "passive"))
      (node (ref "C12") (pin "2") (pinfunction "2_2") (pintype "passive"))
      (node (ref "C13") (pin "1") (pinfunction "1_1") (pintype "passive"))
      (node (ref "C14") (pin "2") (pinfunction "2_2") (pintype "passive"))
      (node (ref "C15") (pin "1") (pinfunction "1_1") (pintype "passive"))
      (node (ref "C16") (pin "2") (pinfunction "2_2") (pintype "passive"))
      (node (ref "C17") (pin "1") (pinfunction "1_1") (pintype "passive"))
      (node (ref "C18") (pin "2") (pinfunction "2_2") (pintype "passive"))
      (node (ref "C19") (pin "1") (pinfunction "1_1") (pintype "passive"))
      (node (ref "C2") (pin "2") (pinfunction "2_2") (pintype "passive"))
      (node (ref "C20") (pin "2") (pinfunction "2_2") (pintype "passive"))
      (node (ref "C21") (pin "1") (pinfunction "1_1") (pintype "passive"))
      (node (ref "C22") (pin "2") (pinfunction "2_2") (pintype "passive"))
      (node (ref "C23") (pin "1") (pinfunction "1_1") (pintype "passive"))
      (node (ref "C24") (pin "2") (pinfunction "2_2") (pintype "passive"))
      (node (ref "C25") (pin "1") (pinfunction "1_1") (pintype "passive"))
      (node (ref "C26") (pin "2") (pinfunction "2_2") (pintype "passive"))
      (node (ref "C27") (pin "1") (pinfunction "1_1") (pintype "passive"))
      (node (ref "C28") (pin "2") (pinfunction "2_2") (pintype "passive"))
      (node (ref "C29") (pin "1") (pinfunction "1_1") (pintype "passive"))
      (node (ref "C3") (pin "1") (pinfunction "1_1") (pintype "passive"))
      (node (ref "C30") (pin "2") (pinfunction "2_2") (pintype "passive"))
      (node (ref "C31") (pin "1") (pinfunction "1_1") (pintype "passive"))
      (node (ref "C32") (pin "2") (pinfunction "2_2") (pintype "passive"))
      (node (ref "C4") (pin "2") (pinfunction "2_2") (pintype "passive"))
      (node (ref "C5") (pin "1") (pinfunction "1_1") (pintype "passive"))
      (node (ref "C6") (pin "2") (pinfunction "2_2") (pintype "passive"))
      (node (ref "C7") (pin "1") (pinfunction "1_1") (pintype "passive"))
      (node (ref "C8") (pin "2") (pinfunction "2_2") (pintype "passive"))
      (node (ref "C9") (pin "1") (pinfunction "1_1") (pintype "passive"))
      (node (ref "R13") (pin "1") (pinfunction "1_1") (pintype "passive"))
      (node (ref "R14") (pin "1") (pinfunction "1_1") (pintype "passive"))
      (node (ref "R15") (pin "1") (pinfunction "1_1") (pintype "passive"))
      (node (ref "R16") (pin "1") (pinfunction "1_1") (pintype "passive"))
      (node (ref "R17") (pin "1") (pinfunction "1_1") (pintype "passive"))
      (node (ref "R18") (pin "1") (pinfunction "1_1") (pintype "passive"))
      (node (ref "R31") (pin "1") (pinfunction "1_1") (pintype "passive"))
      (node (ref "R32") (pin "1") (pinfunction "1_1") (pintype "passive"))
      (node (ref "R33") (pin "1") (pinfunction "1_1") (pintype "passive"))
      (node (ref "R34") (pin "1") (pinfunction "1_1") (pintype "passive"))
      (node (ref "R35") (pin "1") (pinfunction "1_1") (pintype "passive"))
      (node (ref "R36") (pin "1") (pinfunction "1_1") (pintype "passive"))
      (node (ref "R45") (pin "1") (pinfunction "1_1") (pintype "passive"))
      (node (ref "R46") (pin "1") (pinfunction "1_1") (pintype "passive"))
      (node (ref "R47") (pin "1") (pinfunction "1_1") (pintype "passive"))
      (node (ref "R48") (pin "1") (pinfunction "1_1") (pintype "passive"))
      (node (ref "U10") (pin "4") (pinfunction "GND_4") (pintype "passive"))
      (node (ref "U11") (pin "4") (pinfunction "GND_4") (pintype "passive"))
      (node (ref "U12") (pin "4") (pinfunction "GND_4") (pintype "passive"))
      (node (ref "U12") (pin "5") (pinfunction "DIR_5") (pintype "passive"))
      (node (ref "U13") (pin "4") (pinfunction "GND_4") (pintype "passive"))
      (node (ref "U13") (pin "5") (pinfunction "DIR_5") (pintype "passive"))
      (node (ref "U14") (pin "4") (pinfunction "GND_4") (pintype "passive"))
      (node (ref "U14") (pin "5") (pinfunction "DIR_5") (pintype "passive"))
      (node (ref "U15") (pin "4") (pinfunction "GND_4") (pintype "passive"))
      (node (ref "U16") (pin "4") (pinfunction "GND_4") (pintype "passive"))
      (node (ref "U17") (pin "4") (pinfunction "GND_4") (pintype "passive"))
      (node (ref "U17") (pin "5") (pinfunction "DIR_5") (pintype "passive"))
      (node (ref "U18") (pin "4") (pinfunction "GND_4") (pintype "passive"))
      (node (ref "U18") (pin "5") (pinfunction "DIR_5") (pintype "passive"))
      (node (ref "U3") (pin "4") (pinfunction "GND_4") (pintype "passive"))
      (node (ref "U4") (pin "4") (pinfunction "GND_4") (pintype "passive"))
      (node (ref "U5") (pin "4") (pinfunction "GND_4") (pintype "passive"))
      (node (ref "U6") (pin "4") (pinfunction "GND_4") (pintype "passive"))
      (node (ref "U6") (pin "5") (pinfunction "DIR_5") (pintype "passive"))
      (node (ref "U7") (pin "4") (pinfunction "GND_4") (pintype "passive"))
      (node (ref "U7") (pin "5") (pinfunction "DIR_5") (pintype "passive"))
      (node (ref "U8") (pin "4") (pinfunction "GND_4") (pintype "passive"))
      (node (ref "U8") (pin "5") (pinfunction "DIR_5") (pintype "passive"))
      (node (ref "U9") (pin "4") (pinfunction "GND_4") (pintype "passive"))
    )
    (net (code "69") (name "IO-1-2-out") (class "Default")
      (node (ref "C3") (pin "2") (pinfunction "2_2") (pintype "passive"))
      (node (ref "U4") (pin "1") (pinfunction "VCCA_1") (pintype "passive"))
    )
    (net (code "70") (name "IO-3-4-out") (class "Default")
      (node (ref "C15") (pin "2") (pinfunction "2_2") (pintype "passive"))
      (node (ref "U10") (pin "1") (pinfunction "VCCA_1") (pintype "passive"))
    )
    (net (code "71") (name "IO-5-6-out") (class "Default")
      (node (ref "C5") (pin "2") (pinfunction "2_2") (pintype "passive"))
      (node (ref "U5") (pin "1") (pinfunction "VCCA_1") (pintype "passive"))
    )
    (net (code "72") (name "IO-7-8-out") (class "Default")
      (node (ref "C25") (pin "2") (pinfunction "2_2") (pintype "passive"))
      (node (ref "U15") (pin "1") (pinfunction "VCCA_1") (pintype "passive"))
    )
    (net (code "73") (name "IO-9-10-out") (class "Default")
      (node (ref "C27") (pin "2") (pinfunction "2_2") (pintype "passive"))
      (node (ref "U16") (pin "1") (pinfunction "VCCA_1") (pintype "passive"))
    )
    (net (code "74") (name "IO-11-12-out") (class "Default")
      (node (ref "C17") (pin "2") (pinfunction "2_2") (pintype "passive"))
      (node (ref "U11") (pin "1") (pinfunction "VCCA_1") (pintype "passive"))
    )
    (net (code "75") (name "IO-13-14-out") (class "Default")
      (node (ref "C13") (pin "2") (pinfunction "2_2") (pintype "passive"))
      (node (ref "U9") (pin "1") (pinfunction "VCCA_1") (pintype "passive"))
    )
    (net (code "76") (name "IO-15-16-out") (class "Default")
      (node (ref "C1") (pin "2") (pinfunction "2_2") (pintype "passive"))
      (node (ref "U3") (pin "1") (pinfunction "VCCA_1") (pintype "passive"))
    )
    (net (code "77") (name "Net-(U3-1B)") (class "Default")
      (node (ref "R1") (pin "1") (pinfunction "1_1") (pintype "passive"))
      (node (ref "U3") (pin "7") (pinfunction "1B_7") (pintype "passive"))
    )
    (net (code "78") (name "Net-(U3-2B)") (class "Default")
      (node (ref "R7") (pin "1") (pinfunction "1_1") (pintype "passive"))
      (node (ref "U3") (pin "6") (pinfunction "2B_6") (pintype "passive"))
    )
    (net (code "79") (name "Net-(U4-1B)") (class "Default")
      (node (ref "R2") (pin "1") (pinfunction "1_1") (pintype "passive"))
      (node (ref "U4") (pin "7") (pinfunction "1B_7") (pintype "passive"))
    )
    (net (code "80") (name "Net-(U4-2B)") (class "Default")
      (node (ref "R8") (pin "1") (pinfunction "1_1") (pintype "passive"))
      (node (ref "U4") (pin "6") (pinfunction "2B_6") (pintype "passive"))
    )
    (net (code "81") (name "Net-(U5-1B)") (class "Default")
      (node (ref "R3") (pin "1") (pinfunction "1_1") (pintype "passive"))
      (node (ref "U5") (pin "7") (pinfunction "1B_7") (pintype "passive"))
    )
    (net (code "82") (name "Net-(U5-2B)") (class "Default")
      (node (ref "R9") (pin "1") (pinfunction "1_1") (pintype "passive"))
      (node (ref "U5") (pin "6") (pinfunction "2B_6") (pintype "passive"))
    )
    (net (code "83") (name "Net-(U6-1B)") (class "Default")
      (node (ref "R1") (pin "2") (pinfunction "2_2") (pintype "passive"))
      (node (ref "R13") (pin "2") (pinfunction "2_2") (pintype "passive"))
      (node (ref "RLY13") (pin "2") (pinfunction "2_2") (pintype "passive"))
      (node (ref "U6") (pin "7") (pinfunction "1B_7") (pintype "passive"))
    )
    (net (code "84") (name "Net-(U6-2B)") (class "Default")
      (node (ref "R14") (pin "2") (pinfunction "2_2") (pintype "passive"))
      (node (ref "R7") (pin "2") (pinfunction "2_2") (pintype "passive"))
      (node (ref "RLY14") (pin "2") (pinfunction "2_2") (pintype "passive"))
      (node (ref "U6") (pin "6") (pinfunction "2B_6") (pintype "passive"))
    )
    (net (code "85") (name "Net-(U7-1B)") (class "Default")
      (node (ref "R15") (pin "2") (pinfunction "2_2") (pintype "passive"))
      (node (ref "R2") (pin "2") (pinfunction "2_2") (pintype "passive"))
      (node (ref "RLY1") (pin "2") (pinfunction "2_2") (pintype "passive"))
      (node (ref "U7") (pin "7") (pinfunction "1B_7") (pintype "passive"))
    )
    (net (code "86") (name "Net-(U7-2B)") (class "Default")
      (node (ref "R16") (pin "2") (pinfunction "2_2") (pintype "passive"))
      (node (ref "R8") (pin "2") (pinfunction "2_2") (pintype "passive"))
      (node (ref "RLY2") (pin "2") (pinfunction "2_2") (pintype "passive"))
      (node (ref "U7") (pin "6") (pinfunction "2B_6") (pintype "passive"))
    )
    (net (code "87") (name "Net-(U8-1B)") (class "Default")
      (node (ref "R17") (pin "2") (pinfunction "2_2") (pintype "passive"))
      (node (ref "R3") (pin "2") (pinfunction "2_2") (pintype "passive"))
      (node (ref "RLY7") (pin "2") (pinfunction "2_2") (pintype "passive"))
      (node (ref "U8") (pin "7") (pinfunction "1B_7") (pintype "passive"))
    )
    (net (code "88") (name "Net-(U8-2B)") (class "Default")
      (node (ref "R18") (pin "2") (pinfunction "2_2") (pintype "passive"))
      (node (ref "R9") (pin "2") (pinfunction "2_2") (pintype "passive"))
      (node (ref "RLY8") (pin "2") (pinfunction "2_2") (pintype "passive"))
      (node (ref "U8") (pin "6") (pinfunction "2B_6") (pintype "passive"))
    )
    (net (code "89") (name "Net-(U9-1B)") (class "Default")
      (node (ref "R19") (pin "1") (pinfunction "1_1") (pintype "passive"))
      (node (ref "U9") (pin "7") (pinfunction "1B_7") (pintype "passive"))
    )
    (net (code "90") (name "Net-(U9-2B)") (class "Default")
      (node (ref "R25") (pin "1") (pinfunction "1_1") (pintype "passive"))
      (node (ref "U9") (pin "6") (pinfunction "2B_6") (pintype "passive"))
    )
    (net (code "91") (name "Net-(U10-1B)") (class "Default")
      (node (ref "R20") (pin "1") (pinfunction "1_1") (pintype "passive"))
      (node (ref "U10") (pin "7") (pinfunction "1B_7") (pintype "passive"))
    )
    (net (code "92") (name "Net-(U10-2B)") (class "Default")
      (node (ref "R26") (pin "1") (pinfunction "1_1") (pintype "passive"))
      (node (ref "U10") (pin "6") (pinfunction "2B_6") (pintype "passive"))
    )
    (net (code "93") (name "Net-(U11-1B)") (class "Default")
      (node (ref "R21") (pin "1") (pinfunction "1_1") (pintype "passive"))
      (node (ref "U11") (pin "7") (pinfunction "1B_7") (pintype "passive"))
    )
    (net (code "94") (name "Net-(U11-2B)") (class "Default")
      (node (ref "R27") (pin "1") (pinfunction "1_1") (pintype "passive"))
      (node (ref "U11") (pin "6") (pinfunction "2B_6") (pintype "passive"))
    )
    (net (code "95") (name "Net-(U12-1B)") (class "Default")
      (node (ref "R19") (pin "2") (pinfunction "2_2") (pintype "passive"))
      (node (ref "R31") (pin "2") (pinfunction "2_2") (pintype "passive"))
      (node (ref "RLY15") (pin "2") (pinfunction "2_2") (pintype "passive"))
      (node (ref "U12") (pin "7") (pinfunction "1B_7") (pintype "passive"))
    )
    (net (code "96") (name "Net-(U12-2B)") (class "Default")
      (node (ref "R25") (pin "2") (pinfunction "2_2") (pintype "passive"))
      (node (ref "R32") (pin "2") (pinfunction "2_2") (pintype "passive"))
      (node (ref "RLY16") (pin "2") (pinfunction "2_2") (pintype "passive"))
      (node (ref "U12") (pin "6") (pinfunction "2B_6") (pintype "passive"))
    )
    (net (code "97") (name "Net-(U13-1B)") (class "Default")
      (node (ref "R20") (pin "2") (pinfunction "2_2") (pintype "passive"))
      (node (ref "R33") (pin "2") (pinfunction "2_2") (pintype "passive"))
      (node (ref "RLY3") (pin "2") (pinfunction "2_2") (pintype "passive"))
      (node (ref "U13") (pin "7") (pinfunction "1B_7") (pintype "passive"))
    )
    (net (code "98") (name "Net-(U13-2B)") (class "Default")
      (node (ref "R26") (pin "2") (pinfunction "2_2") (pintype "passive"))
      (node (ref "R34") (pin "2") (pinfunction "2_2") (pintype "passive"))
      (node (ref "RLY4") (pin "2") (pinfunction "2_2") (pintype "passive"))
      (node (ref "U13") (pin "6") (pinfunction "2B_6") (pintype "passive"))
    )
    (net (code "99") (name "Net-(U14-1B)") (class "Default")
      (node (ref "R21") (pin "2") (pinfunction "2_2") (pintype "passive"))
      (node (ref "R35") (pin "2") (pinfunction "2_2") (pintype "passive"))
      (node (ref "RLY9") (pin "2") (pinfunction "2_2") (pintype "passive"))
      (node (ref "U14") (pin "7") (pinfunction "1B_7") (pintype "passive"))
    )
    (net (code "100") (name "Net-(U14-2B)") (class "Default")
      (node (ref "R27") (pin "2") (pinfunction "2_2") (pintype "passive"))
      (node (ref "R36") (pin "2") (pinfunction "2_2") (pintype "passive"))
      (node (ref "RLY10") (pin "2") (pinfunction "2_2") (pintype "passive"))
      (node (ref "U14") (pin "6") (pinfunction "2B_6") (pintype "passive"))
    )
    (net (code "101") (name "Net-(U15-1B)") (class "Default")
      (node (ref "R37") (pin "1") (pinfunction "1_1") (pintype "passive"))
      (node (ref "U15") (pin "7") (pinfunction "1B_7") (pintype "passive"))
    )
    (net (code "102") (name "Net-(U15-2B)") (class "Default")
      (node (ref "R41") (pin "1") (pinfunction "1_1") (pintype "passive"))
      (node (ref "U15") (pin "6") (pinfunction "2B_6") (pintype "passive"))
    )
    (net (code "103") (name "Net-(U16-1B)") (class "Default")
      (node (ref "R38") (pin "1") (pinfunction "1_1") (pintype "passive"))
      (node (ref "U16") (pin "7") (pinfunction "1B_7") (pintype "passive"))
    )
    (net (code "104") (name "Net-(U16-2B)") (class "Default")
      (node (ref "R42") (pin "1") (pinfunction "1_1") (pintype "passive"))
      (node (ref "U16") (pin "6") (pinfunction "2B_6") (pintype "passive"))
    )
    (net (code "105") (name "Net-(U17-1B)") (class "Default")
      (node (ref "R37") (pin "2") (pinfunction "2_2") (pintype "passive"))
      (node (ref "R45") (pin "2") (pinfunction "2_2") (pintype "passive"))
      (node (ref "RLY5") (pin "2") (pinfunction "2_2") (pintype "passive"))
      (node (ref "U17") (pin "7") (pinfunction "1B_7") (pintype "passive"))
    )
    (net (code "106") (name "Net-(U17-2B)") (class "Default")
      (node (ref "R41") (pin "2") (pinfunction "2_2") (pintype "passive"))
      (node (ref "R46") (pin "2") (pinfunction "2_2") (pintype "passive"))
      (node (ref "RLY6") (pin "2") (pinfunction "2_2") (pintype "passive"))
      (node (ref "U17") (pin "6") (pinfunction "2B_6") (pintype "passive"))
    )
    (net (code "107") (name "Net-(U18-1B)") (class "Default")
      (node (ref "R38") (pin "2") (pinfunction "2_2") (pintype "passive"))
      (node (ref "R47") (pin "2") (pinfunction "2_2") (pintype "passive"))
      (node (ref "RLY11") (pin "2") (pinfunction "2_2") (pintype "passive"))
      (node (ref "U18") (pin "7") (pinfunction "1B_7") (pintype "passive"))
    )
    (net (code "108") (name "Net-(U18-2B)") (class "Default")
      (node (ref "R42") (pin "2") (pinfunction "2_2") (pintype "passive"))
      (node (ref "R48") (pin "2") (pinfunction "2_2") (pintype "passive"))
      (node (ref "RLY12") (pin "2") (pinfunction "2_2") (pintype "passive"))
      (node (ref "U18") (pin "6") (pinfunction "2B_6") (pintype "passive"))
    )
  )
)
